# Teensy_SD_with_Amp.net
KiCad netlist of a schematic drawn in EAGLE
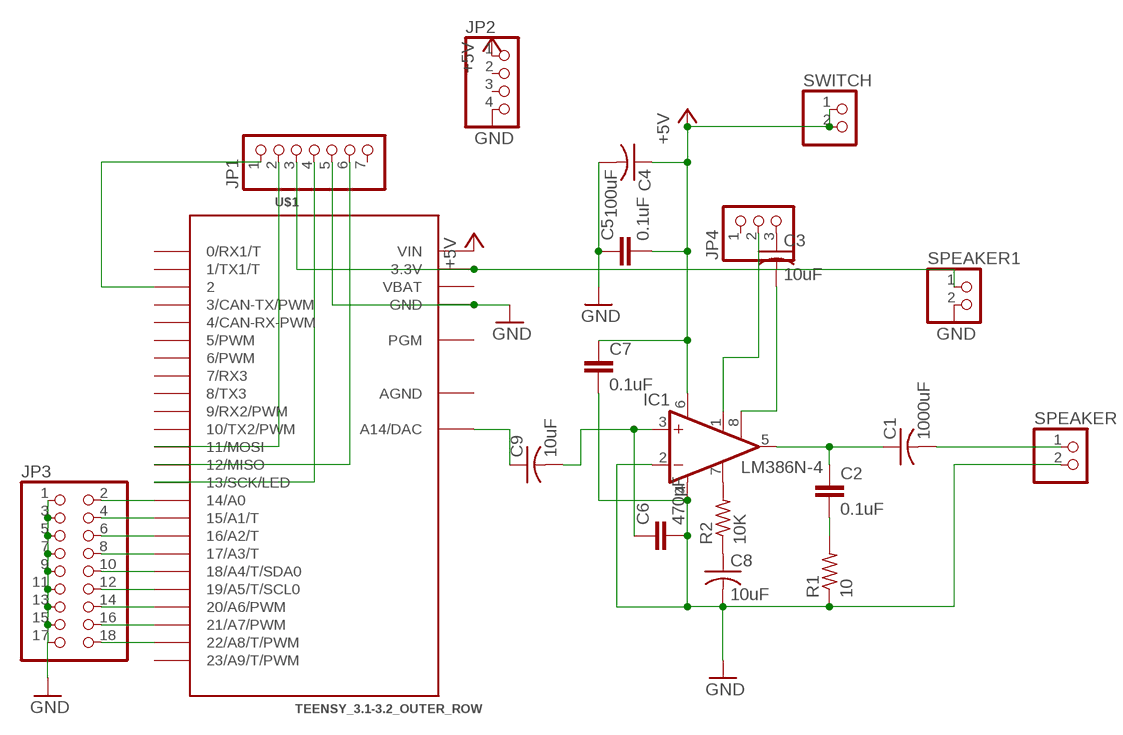
[diagram p0: schematic, sheet 1]

(export (version "E")
  (design (tool "Eeschema 10.0.6"))
  (components
    (comp (ref "C1")
      (value "1000uF")
      (footprint "eagle-import:C025-030X050")
      (libsource (lib "eagle-import") (part "C-US025-030X050"))
    )
    (comp (ref "C2")
      (value "0.1uF")
      (footprint "eagle-import:C2.5-4")
      (libsource (lib "eagle-import") (part "C2.5/4"))
    )
    (comp (ref "C3")
      (value "10uF")
      (footprint "eagle-import:C025-030X050")
      (libsource (lib "eagle-import") (part "C-US025-030X050"))
    )
    (comp (ref "C4")
      (value "100uF")
      (footprint "eagle-import:C025-030X050")
      (libsource (lib "eagle-import") (part "C-US025-030X050"))
    )
    (comp (ref "C5")
      (value "0.1uF")
      (footprint "eagle-import:C2.5-4")
      (libsource (lib "eagle-import") (part "C2.5/4"))
    )
    (comp (ref "C6")
      (value "470pF")
      (footprint "eagle-import:C2.5-4")
      (libsource (lib "eagle-import") (part "C2.5/4"))
    )
    (comp (ref "C7")
      (value "0.1uF")
      (footprint "eagle-import:C2.5-4")
      (libsource (lib "eagle-import") (part "C2.5/4"))
    )
    (comp (ref "C8")
      (value "10uF")
      (footprint "eagle-import:C025-030X050")
      (libsource (lib "eagle-import") (part "C-US025-030X050"))
    )
    (comp (ref "C9")
      (value "10uF")
      (footprint "eagle-import:C025-030X050")
      (libsource (lib "eagle-import") (part "C-US025-030X050"))
    )
    (comp (ref "IC1")
      (value "LM386N-4")
      (footprint "eagle-import:DIL08")
      (libsource (lib "eagle-import") (part "LM386?-N4"))
    )
    (comp (ref "JP1")
      (value "PINHD-1X7")
      (footprint "eagle-import:1X07")
      (libsource (lib "eagle-import") (part "PINHD-1X7"))
    )
    (comp (ref "JP2")
      (value "PINHD-1X4")
      (footprint "eagle-import:1X04")
      (libsource (lib "eagle-import") (part "PINHD-1X4"))
    )
    (comp (ref "JP3")
      (value "PINHD-2X9")
      (footprint "eagle-import:2X09")
      (libsource (lib "eagle-import") (part "PINHD-2X9"))
    )
    (comp (ref "JP4")
      (value "PINHD-1X3")
      (footprint "eagle-import:1X03")
      (libsource (lib "eagle-import") (part "PINHD-1X3"))
    )
    (comp (ref "R1")
      (value "10")
      (footprint "eagle-import:0207_7")
      (libsource (lib "eagle-import") (part "R-US_0207/7"))
    )
    (comp (ref "R2")
      (value "10K")
      (footprint "eagle-import:0207_7")
      (libsource (lib "eagle-import") (part "R-US_0207/7"))
    )
    (comp (ref "SPEAKER")
      (value "PINHD-1X2")
      (footprint "eagle-import:1X02")
      (libsource (lib "eagle-import") (part "PINHD-1X2"))
    )
    (comp (ref "SPEAKER1")
      (value "PINHD-1X2")
      (footprint "eagle-import:1X02")
      (libsource (lib "eagle-import") (part "PINHD-1X2"))
    )
    (comp (ref "SWITCH")
      (value "PINHD-1X2")
      (footprint "eagle-import:1X02")
      (libsource (lib "eagle-import") (part "PINHD-1X2"))
    )
    (comp (ref "U$1")
      (value "TEENSY_3.1-3.2_OUTER_ROW")
      (footprint "eagle-import:TEENSY_3.0-3.2&LC_OUTER_ROW")
      (libsource (lib "eagle-import") (part "TEENSY_3.1-3.2_OUTER_ROW"))
    )
  )
  (nets
    (net (code "1") (name "+5V") (class "Default")
      (node (ref "C4") (pin "1") (pinfunction "1_1") (pintype "passive"))
      (node (ref "C5") (pin "2") (pinfunction "2_2") (pintype "passive"))
      (node (ref "C7") (pin "1") (pinfunction "1_1") (pintype "passive"))
      (node (ref "IC1") (pin "6") (pinfunction "VS_6") (pintype "power_in"))
      (node (ref "JP2") (pin "1") (pinfunction "1_1") (pintype "passive"))
      (node (ref "SWITCH") (pin "1") (pinfunction "1_1") (pintype "passive"))
      (node (ref "SWITCH") (pin "2") (pinfunction "2_2") (pintype "passive"))
      (node (ref "U$1") (pin "VIN") (pinfunction "VIN_VIN") (pintype "power_in"))
    )
    (net (code "2") (name "/AGND") (class "Default")
      (node (ref "U$1") (pin "AGND") (pinfunction "AGND_AGND") (pintype "power_in"))
    )
    (net (code "3") (name "/VBAT") (class "Default")
      (node (ref "U$1") (pin "VBAT") (pinfunction "VBAT_VBAT") (pintype "power_in"))
    )
    (net (code "4") (name "GND") (class "Default")
      (node (ref "C4") (pin "2") (pinfunction "2_2") (pintype "passive"))
      (node (ref "C5") (pin "1") (pinfunction "1_1") (pintype "passive"))
      (node (ref "C6") (pin "2") (pinfunction "2_2") (pintype "passive"))
      (node (ref "C7") (pin "2") (pinfunction "2_2") (pintype "passive"))
      (node (ref "C8") (pin "2") (pinfunction "2_2") (pintype "passive"))
      (node (ref "IC1") (pin "2") (pinfunction "-IN_2") (pintype "input"))
      (node (ref "IC1") (pin "4") (pinfunction "GND_4") (pintype "power_in"))
      (node (ref "JP1") (pin "5") (pinfunction "5_5") (pintype "passive"))
      (node (ref "JP2") (pin "4") (pinfunction "4_4") (pintype "passive"))
      (node (ref "JP3") (pin "1") (pinfunction "1_1") (pintype "passive"))
      (node (ref "JP3") (pin "11") (pinfunction "11_11") (pintype "passive"))
      (node (ref "JP3") (pin "13") (pinfunction "13_13") (pintype "passive"))
      (node (ref "JP3") (pin "15") (pinfunction "15_15") (pintype "passive"))
      (node (ref "JP3") (pin "17") (pinfunction "17_17") (pintype "passive"))
      (node (ref "JP3") (pin "3") (pinfunction "3_3") (pintype "passive"))
      (node (ref "JP3") (pin "5") (pinfunction "5_5") (pintype "passive"))
      (node (ref "JP3") (pin "7") (pinfunction "7_7") (pintype "passive"))
      (node (ref "JP3") (pin "9") (pinfunction "9_9") (pintype "passive"))
      (node (ref "R1") (pin "1") (pinfunction "1_1") (pintype "passive"))
      (node (ref "SPEAKER") (pin "2") (pinfunction "2_2") (pintype "passive"))
      (node (ref "SPEAKER1") (pin "2") (pinfunction "2_2") (pintype "passive"))
      (node (ref "U$1") (pin "GND") (pinfunction "GND_GND") (pintype "power_in"))
      (node (ref "U$1") (pin "GND1") (pinfunction "GND_GND1") (pintype "power_in"))
    )
    (net (code "5") (name "Net-(C1-Pad2)") (class "Default")
      (node (ref "C1") (pin "2") (pinfunction "2_2") (pintype "passive"))
      (node (ref "SPEAKER") (pin "1") (pinfunction "1_1") (pintype "passive"))
    )
    (net (code "6") (name "Net-(C2-Pad2)") (class "Default")
      (node (ref "C2") (pin "2") (pinfunction "2_2") (pintype "passive"))
      (node (ref "R1") (pin "2") (pinfunction "2_2") (pintype "passive"))
    )
    (net (code "7") (name "Net-(C3-Pad1)") (class "Default")
      (node (ref "C3") (pin "1") (pinfunction "1_1") (pintype "passive"))
      (node (ref "JP4") (pin "3") (pinfunction "3_3") (pintype "passive"))
    )
    (net (code "8") (name "Net-(C3-Pad2)") (class "Default")
      (node (ref "C3") (pin "2") (pinfunction "2_2") (pintype "passive"))
      (node (ref "IC1") (pin "8") (pinfunction "GAIN_8") (pintype "passive"))
    )
    (net (code "9") (name "Net-(C8-Pad1)") (class "Default")
      (node (ref "C8") (pin "1") (pinfunction "1_1") (pintype "passive"))
      (node (ref "R2") (pin "1") (pinfunction "1_1") (pintype "passive"))
    )
    (net (code "10") (name "Net-(IC1-+IN)") (class "Default")
      (node (ref "C6") (pin "1") (pinfunction "1_1") (pintype "passive"))
      (node (ref "C9") (pin "2") (pinfunction "2_2") (pintype "passive"))
      (node (ref "IC1") (pin "3") (pinfunction "+IN_3") (pintype "input"))
    )
    (net (code "11") (name "Net-(IC1-BYPASS)") (class "Default")
      (node (ref "IC1") (pin "7") (pinfunction "BYPASS_7") (pintype "passive"))
      (node (ref "R2") (pin "2") (pinfunction "2_2") (pintype "passive"))
    )
    (net (code "12") (name "Net-(IC1-GAIN-Pad1)") (class "Default")
      (node (ref "IC1") (pin "1") (pinfunction "GAIN_1") (pintype "passive"))
      (node (ref "JP4") (pin "2") (pinfunction "2_2") (pintype "passive"))
    )
    (net (code "13") (name "Net-(IC1-OUT)") (class "Default")
      (node (ref "C1") (pin "1") (pinfunction "1_1") (pintype "passive"))
      (node (ref "C2") (pin "1") (pinfunction "1_1") (pintype "passive"))
      (node (ref "IC1") (pin "5") (pinfunction "OUT_5") (pintype "output"))
    )
    (net (code "14") (name "Net-(JP1-Pad1)") (class "Default")
      (node (ref "JP1") (pin "1") (pinfunction "1_1") (pintype "passive"))
      (node (ref "U$1") (pin "2") (pinfunction "2_2") (pintype "bidirectional"))
    )
    (net (code "15") (name "Net-(JP1-Pad3)") (class "Default")
      (node (ref "JP1") (pin "3") (pinfunction "3_3") (pintype "passive"))
      (node (ref "SPEAKER1") (pin "1") (pinfunction "1_1") (pintype "passive"))
      (node (ref "U$1") (pin "3.3V") (pinfunction "3.3V_3.3V") (pintype "power_in"))
      (node (ref "U$1") (pin "3.3V1") (pinfunction "3.3V_3.3V1") (pintype "power_in"))
    )
    (net (code "16") (name "Net-(JP3-Pad2)") (class "Default")
      (node (ref "JP3") (pin "2") (pinfunction "2_2") (pintype "passive"))
      (node (ref "U$1") (pin "14/A0") (pinfunction "14/A0_14/A0") (pintype "bidirectional"))
    )
    (net (code "17") (name "Net-(U$1-11{slash}MOSI)") (class "Default")
      (node (ref "JP1") (pin "2") (pinfunction "2_2") (pintype "passive"))
      (node (ref "U$1") (pin "11") (pinfunction "11/MOSI_11") (pintype "bidirectional"))
    )
    (net (code "18") (name "Net-(U$1-12{slash}MISO)") (class "Default")
      (node (ref "JP1") (pin "6") (pinfunction "6_6") (pintype "passive"))
      (node (ref "U$1") (pin "12") (pinfunction "12/MISO_12") (pintype "bidirectional"))
    )
    (net (code "19") (name "Net-(U$1-13{slash}SCK{slash}LED)") (class "Default")
      (node (ref "JP1") (pin "4") (pinfunction "4_4") (pintype "passive"))
      (node (ref "U$1") (pin "13") (pinfunction "13/SCK/LED_13") (pintype "bidirectional"))
    )
    (net (code "20") (name "Net-(U$1-15{slash}A1{slash}T)") (class "Default")
      (node (ref "JP3") (pin "4") (pinfunction "4_4") (pintype "passive"))
      (node (ref "U$1") (pin "15/A1") (pinfunction "15/A1/T_15/A1") (pintype "bidirectional"))
    )
    (net (code "21") (name "Net-(U$1-16{slash}A2{slash}T)") (class "Default")
      (node (ref "JP3") (pin "6") (pinfunction "6_6") (pintype "passive"))
      (node (ref "U$1") (pin "16/A2") (pinfunction "16/A2/T_16/A2") (pintype "bidirectional"))
    )
    (net (code "22") (name "Net-(U$1-17{slash}A3{slash}T)") (class "Default")
      (node (ref "JP3") (pin "8") (pinfunction "8_8") (pintype "passive"))
      (node (ref "U$1") (pin "17/A3") (pinfunction "17/A3/T_17/A3") (pintype "bidirectional"))
    )
    (net (code "23") (name "Net-(U$1-18{slash}A4{slash}T{slash}SDA0)") (class "Default")
      (node (ref "JP3") (pin "10") (pinfunction "10_10") (pintype "passive"))
      (node (ref "U$1") (pin "18/A4") (pinfunction "18/A4/T/SDA0_18/A4") (pintype "bidirectional"))
    )
    (net (code "24") (name "Net-(U$1-19{slash}A5{slash}T{slash}SCL0)") (class "Default")
      (node (ref "JP3") (pin "12") (pinfunction "12_12") (pintype "passive"))
      (node (ref "U$1") (pin "19/A5") (pinfunction "19/A5/T/SCL0_19/A5") (pintype "bidirectional"))
    )
    (net (code "25") (name "Net-(U$1-20{slash}A6{slash}PWM)") (class "Default")
      (node (ref "JP3") (pin "14") (pinfunction "14_14") (pintype "passive"))
      (node (ref "U$1") (pin "20/A6") (pinfunction "20/A6/PWM_20/A6") (pintype "bidirectional"))
    )
    (net (code "26") (name "Net-(U$1-21{slash}A7{slash}PWM)") (class "Default")
      (node (ref "JP3") (pin "16") (pinfunction "16_16") (pintype "passive"))
      (node (ref "U$1") (pin "21/A7") (pinfunction "21/A7/PWM_21/A7") (pintype "bidirectional"))
    )
    (net (code "27") (name "Net-(U$1-22{slash}A8{slash}T{slash}PWM)") (class "Default")
      (node (ref "JP3") (pin "18") (pinfunction "18_18") (pintype "passive"))
      (node (ref "U$1") (pin "22/A8") (pinfunction "22/A8/T/PWM_22/A8") (pintype "bidirectional"))
    )
    (net (code "28") (name "Net-(U$1-A14{slash}DAC)") (class "Default")
      (node (ref "C9") (pin "1") (pinfunction "1_1") (pintype "passive"))
      (node (ref "U$1") (pin "RESET/DAC") (pinfunction "A14/DAC_RESET/DAC") (pintype "bidirectional"))
    )
    (net (code "29") (name "unconnected-(JP1-Pad7)") (class "Default")
      (node (ref "JP1") (pin "7") (pinfunction "7_7") (pintype "passive"))
    )
    (net (code "30") (name "unconnected-(JP2-Pad2)") (class "Default")
      (node (ref "JP2") (pin "2") (pinfunction "2_2") (pintype "passive"))
    )
    (net (code "31") (name "unconnected-(JP2-Pad3)") (class "Default")
      (node (ref "JP2") (pin "3") (pinfunction "3_3") (pintype "passive"))
    )
    (net (code "32") (name "unconnected-(JP4-Pad1)") (class "Default")
      (node (ref "JP4") (pin "1") (pinfunction "1_1") (pintype "passive"))
    )
    (net (code "33") (name "unconnected-(U$1-0{slash}RX1{slash}T-Pad0)") (class "Default")
      (node (ref "U$1") (pin "0") (pinfunction "0/RX1/T_0") (pintype "bidirectional"))
    )
    (net (code "34") (name "unconnected-(U$1-1{slash}TX1{slash}T-Pad1)") (class "Default")
      (node (ref "U$1") (pin "1") (pinfunction "1/TX1/T_1") (pintype "bidirectional"))
    )
    (net (code "35") (name "unconnected-(U$1-3{slash}CAN-TX{slash}PWM-Pad3)") (class "Default")
      (node (ref "U$1") (pin "3") (pinfunction "3/CAN-TX/PWM_3") (pintype "bidirectional"))
    )
    (net (code "36") (name "unconnected-(U$1-4{slash}CAN-RX-PWM-Pad4)") (class "Default")
      (node (ref "U$1") (pin "4") (pinfunction "4/CAN-RX-PWM_4") (pintype "bidirectional"))
    )
    (net (code "37") (name "unconnected-(U$1-5{slash}PWM-Pad5)") (class "Default")
      (node (ref "U$1") (pin "5") (pinfunction "5/PWM_5") (pintype "bidirectional"))
    )
    (net (code "38") (name "unconnected-(U$1-6{slash}PWM-Pad6)") (class "Default")
      (node (ref "U$1") (pin "6") (pinfunction "6/PWM_6") (pintype "bidirectional"))
    )
    (net (code "39") (name "unconnected-(U$1-7{slash}RX3-Pad7)") (class "Default")
      (node (ref "U$1") (pin "7") (pinfunction "7/RX3_7") (pintype "bidirectional"))
    )
    (net (code "40") (name "unconnected-(U$1-8{slash}TX3-Pad8)") (class "Default")
      (node (ref "U$1") (pin "8") (pinfunction "8/TX3_8") (pintype "bidirectional"))
    )
    (net (code "41") (name "unconnected-(U$1-9{slash}RX2{slash}PWM-Pad9)") (class "Default")
      (node (ref "U$1") (pin "9") (pinfunction "9/RX2/PWM_9") (pintype "bidirectional"))
    )
    (net (code "42") (name "unconnected-(U$1-10{slash}TX2{slash}PWM-Pad10)") (class "Default")
      (node (ref "U$1") (pin "10") (pinfunction "10/TX2/PWM_10") (pintype "bidirectional"))
    )
    (net (code "43") (name "unconnected-(U$1-23{slash}A9{slash}T{slash}PWM-Pad23{slash}A9)") (class "Default")
      (node (ref "U$1") (pin "23/A9") (pinfunction "23/A9/T/PWM_23/A9") (pintype "bidirectional"))
    )
    (net (code "44") (name "unconnected-(U$1-PadPGM)") (class "Default")
      (node (ref "U$1") (pin "PGM") (pinfunction "PGM_PGM") (pintype "bidirectional"))
    )
  )
)
